# imu.net
KiCad netlist of a schematic drawn in Altium Designer
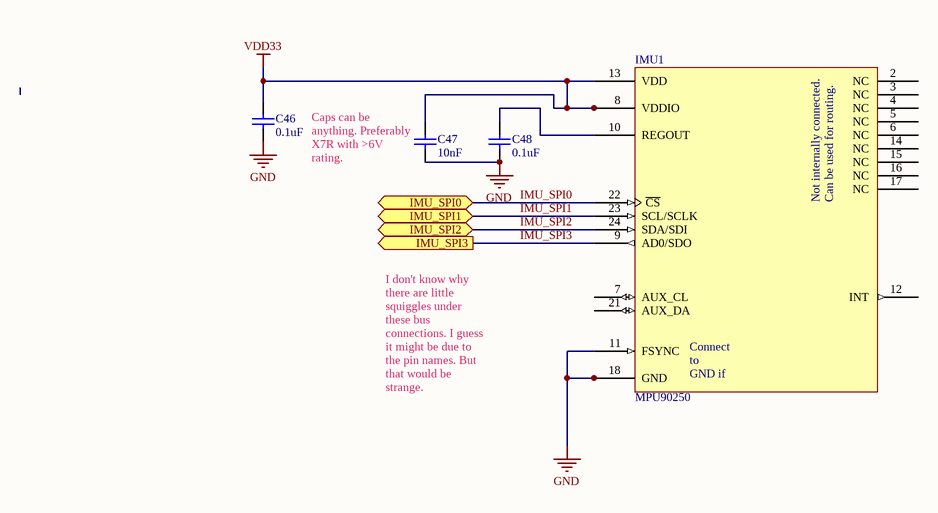
[diagram p0: imu.SchDoc]

(export (version "E")
  (design (tool "Eeschema 10.0.6"))
  (components
    (comp (ref "C46")
      (value "0.1uF")
      (footprint "Cap_0402")
      (description "Capacitor")
      (fields (field (name "Comment") "Cap") (field (name "PUBLISHER") "Altium Limited"))
      (libsource (lib "Miscellaneous Devices") (part "Cap"))
    )
    (comp (ref "C47")
      (value "10nF")
      (footprint "Cap_0402")
      (description "Capacitor")
      (fields (field (name "Comment") "Cap") (field (name "PUBLISHER") "Altium Limited"))
      (libsource (lib "Miscellaneous Devices") (part "Cap"))
    )
    (comp (ref "C48")
      (value "0.1uF")
      (footprint "Cap_0402")
      (description "Capacitor")
      (fields (field (name "Comment") "Cap") (field (name "PUBLISHER") "Altium Limited"))
      (libsource (lib "Miscellaneous Devices") (part "Cap"))
    )
    (comp (ref "IMU1")
      (value "MPU90250")
      (footprint "QFN24-3x3mm")
      (description "9-Axis IMU (Accel, Gyro, Magno)")
      (libsource (lib "jonnew") (part "MPU90250"))
    )
  )
  (nets
    (net (code "1") (name "/IMU_SPI0") (class "Default")
      (node (ref "IMU1") (pin "22") (pinfunction "~{CS}_22") (pintype "input"))
    )
    (net (code "2") (name "/IMU_SPI1") (class "Default")
      (node (ref "IMU1") (pin "23") (pinfunction "SCL/SCLK_23") (pintype "input"))
    )
    (net (code "3") (name "/IMU_SPI2") (class "Default")
      (node (ref "IMU1") (pin "24") (pinfunction "SDA/SDI_24") (pintype "input"))
    )
    (net (code "4") (name "/IMU_SPI3") (class "Default")
      (node (ref "IMU1") (pin "9") (pinfunction "AD0/SDO_9") (pintype "output"))
    )
    (net (code "5") (name "GND") (class "Default")
      (node (ref "C46") (pin "2") (pinfunction "2_2") (pintype "passive"))
      (node (ref "C47") (pin "2") (pinfunction "2_2") (pintype "passive"))
      (node (ref "C48") (pin "2") (pinfunction "2_2") (pintype "passive"))
      (node (ref "IMU1") (pin "11") (pinfunction "FSYNC_11") (pintype "input"))
      (node (ref "IMU1") (pin "18") (pinfunction "GND_18") (pintype "power_in"))
      (node (ref "IMU1") (pin "20") (pinfunction "RESV_20") (pintype "power_in"))
    )
    (net (code "6") (name "Net-(IMU1-REGOUT)") (class "Default")
      (node (ref "C48") (pin "1") (pinfunction "1_1") (pintype "passive"))
      (node (ref "IMU1") (pin "10") (pinfunction "REGOUT_10") (pintype "passive"))
    )
    (net (code "7") (name "VDD33") (class "Default")
      (node (ref "C46") (pin "1") (pinfunction "1_1") (pintype "passive"))
      (node (ref "C47") (pin "1") (pinfunction "1_1") (pintype "passive"))
      (node (ref "IMU1") (pin "1") (pinfunction "RESV_1") (pintype "power_in"))
      (node (ref "IMU1") (pin "13") (pinfunction "VDD_13") (pintype "passive"))
      (node (ref "IMU1") (pin "8") (pinfunction "VDDIO_8") (pintype "power_in"))
    )
    (net (code "8") (name "unconnected-(IMU1-AUX_CL-Pad7)") (class "Default")
      (node (ref "IMU1") (pin "7") (pinfunction "AUX_CL_7") (pintype "bidirectional"))
    )
    (net (code "9") (name "unconnected-(IMU1-AUX_DA-Pad21)") (class "Default")
      (node (ref "IMU1") (pin "21") (pinfunction "AUX_DA_21") (pintype "bidirectional"))
    )
    (net (code "10") (name "unconnected-(IMU1-DO_NOT_CONNECT-Pad19)") (class "Default")
      (node (ref "IMU1") (pin "19") (pinfunction "DO_NOT_CONNECT_19") (pintype "passive"))
    )
    (net (code "11") (name "unconnected-(IMU1-INT-Pad12)") (class "Default")
      (node (ref "IMU1") (pin "12") (pinfunction "INT_12") (pintype "output"))
    )
    (net (code "12") (name "unconnected-(IMU1-NC-Pad2)") (class "Default")
      (node (ref "IMU1") (pin "2") (pinfunction "NC_2") (pintype "passive"))
    )
    (net (code "13") (name "unconnected-(IMU1-NC-Pad3)") (class "Default")
      (node (ref "IMU1") (pin "3") (pinfunction "NC_3") (pintype "passive"))
    )
    (net (code "14") (name "unconnected-(IMU1-NC-Pad4)") (class "Default")
      (node (ref "IMU1") (pin "4") (pinfunction "NC_4") (pintype "passive"))
    )
    (net (code "15") (name "unconnected-(IMU1-NC-Pad5)") (class "Default")
      (node (ref "IMU1") (pin "5") (pinfunction "NC_5") (pintype "passive"))
    )
    (net (code "16") (name "unconnected-(IMU1-NC-Pad6)") (class "Default")
      (node (ref "IMU1") (pin "6") (pinfunction "NC_6") (pintype "passive"))
    )
    (net (code "17") (name "unconnected-(IMU1-NC-Pad14)") (class "Default")
      (node (ref "IMU1") (pin "14") (pinfunction "NC_14") (pintype "passive"))
    )
    (net (code "18") (name "unconnected-(IMU1-NC-Pad15)") (class "Default")
      (node (ref "IMU1") (pin "15") (pinfunction "NC_15") (pintype "passive"))
    )
    (net (code "19") (name "unconnected-(IMU1-NC-Pad16)") (class "Default")
      (node (ref "IMU1") (pin "16") (pinfunction "NC_16") (pintype "passive"))
    )
    (net (code "20") (name "unconnected-(IMU1-NC-Pad17)") (class "Default")
      (node (ref "IMU1") (pin "17") (pinfunction "NC_17") (pintype "passive"))
    )
  )
)
